# Retro_Programmer-v0_2.net
KiCad netlist of a schematic drawn in EAGLE
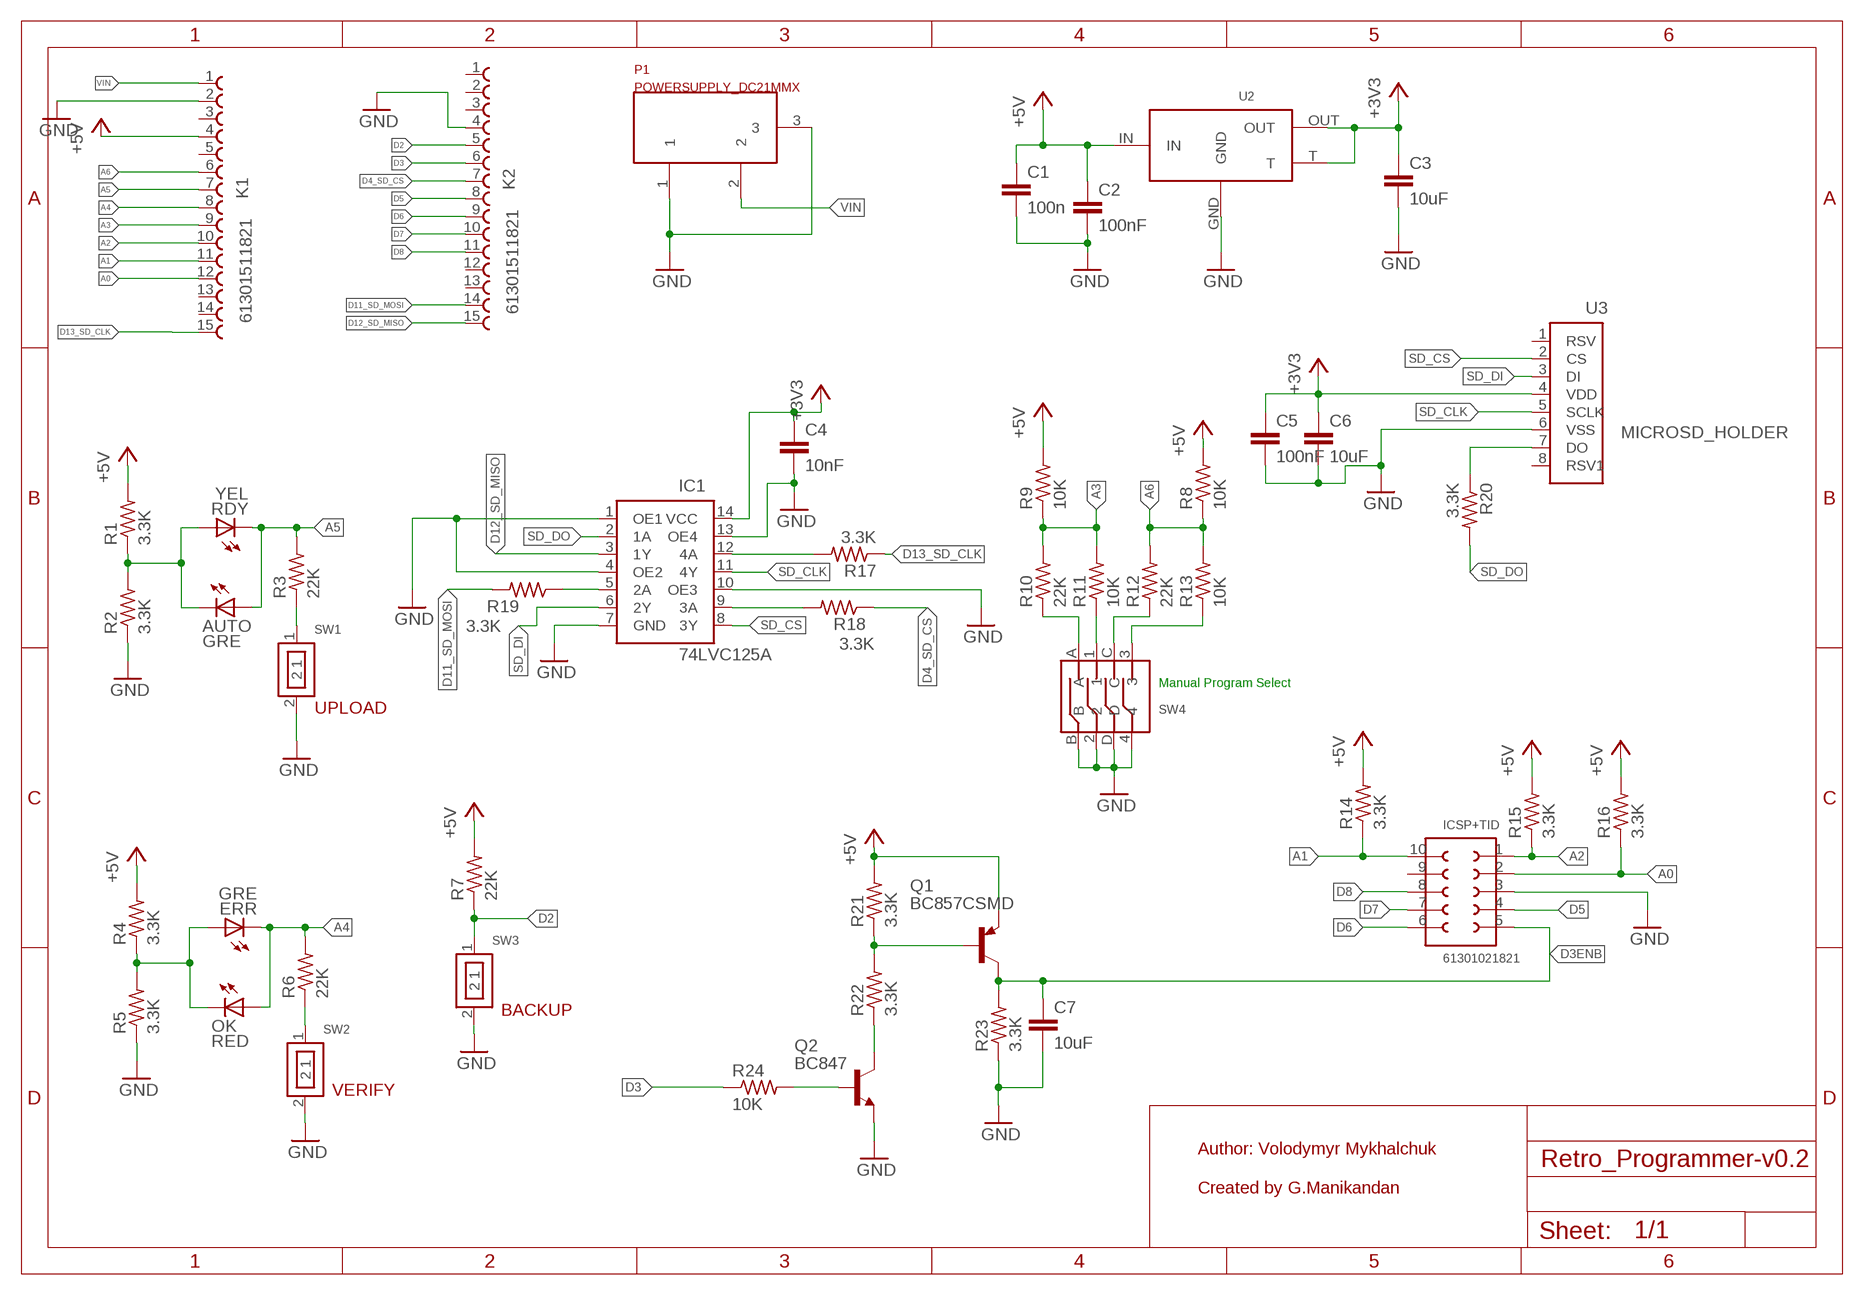
[diagram p0: schematic, sheet 1]

(export (version "E")
  (design (tool "Eeschema 10.0.6"))
  (components
    (comp (ref "AUTO")
      (value "GRE")
      (footprint "eagle-import:CHIPLED_1206")
      (libsource (lib "eagle-import") (part "LEDCHIPLED_1206"))
    )
    (comp (ref "C1")
      (value "100n")
      (footprint "eagle-import:C1206")
      (libsource (lib "eagle-import") (part "C-EUC1206"))
    )
    (comp (ref "C2")
      (value "100nF")
      (footprint "eagle-import:C1206")
      (libsource (lib "eagle-import") (part "C-EUC1206"))
    )
    (comp (ref "C3")
      (value "10uF")
      (footprint "eagle-import:C1206")
      (libsource (lib "eagle-import") (part "C-EUC1206"))
    )
    (comp (ref "C4")
      (value "10nF")
      (footprint "eagle-import:C1206")
      (libsource (lib "eagle-import") (part "C-EUC1206"))
    )
    (comp (ref "C5")
      (value "100nF")
      (footprint "eagle-import:C1206")
      (libsource (lib "eagle-import") (part "C-EUC1206"))
    )
    (comp (ref "C6")
      (value "10uF")
      (footprint "eagle-import:C1206")
      (libsource (lib "eagle-import") (part "C-EUC1206"))
    )
    (comp (ref "C7")
      (value "10uF")
      (footprint "eagle-import:C1206")
      (libsource (lib "eagle-import") (part "C-EUC1206"))
    )
    (comp (ref "ERR")
      (value "GRE")
      (footprint "eagle-import:CHIPLED_1206")
      (libsource (lib "eagle-import") (part "LEDCHIPLED_1206"))
    )
    (comp (ref "IC1")
      (value "74LVC125A")
      (footprint "eagle-import:SOIC14_74L")
      (libsource (lib "eagle-import") (part "74LVC125A"))
    )
    (comp (ref "ICSP+TID")
      (value "61301021821")
      (footprint "eagle-import:61301021821")
      (libsource (lib "eagle-import") (part "61301021821"))
    )
    (comp (ref "K1")
      (value "61301511821")
      (footprint "eagle-import:61301511821")
      (libsource (lib "eagle-import") (part "61301511821"))
    )
    (comp (ref "K2")
      (value "61301511821")
      (footprint "eagle-import:61301511821")
      (libsource (lib "eagle-import") (part "61301511821"))
    )
    (comp (ref "OK")
      (value "RED")
      (footprint "eagle-import:CHIPLED_1206")
      (libsource (lib "eagle-import") (part "LEDCHIPLED_1206"))
    )
    (comp (ref "P1")
      (value "POWERSUPPLY_DC21MMX")
      (footprint "eagle-import:POWERSUPPLY_DC-21MM")
      (libsource (lib "eagle-import") (part "POWERSUPPLY_DC21MMX"))
    )
    (comp (ref "Q1")
      (value "BC857CSMD")
      (footprint "eagle-import:SOT23-BEC")
      (libsource (lib "eagle-import") (part "BC857SMDC"))
    )
    (comp (ref "Q2")
      (value "BC847")
      (footprint "eagle-import:SOT23")
      (libsource (lib "eagle-import") (part "BC847"))
    )
    (comp (ref "R1")
      (value "3.3K")
      (footprint "eagle-import:R1206")
      (libsource (lib "eagle-import") (part "R-US_R1206"))
    )
    (comp (ref "R2")
      (value "3.3K")
      (footprint "eagle-import:R1206")
      (libsource (lib "eagle-import") (part "R-US_R1206"))
    )
    (comp (ref "R3")
      (value "22K")
      (footprint "eagle-import:R1206")
      (libsource (lib "eagle-import") (part "R-US_R1206"))
    )
    (comp (ref "R4")
      (value "3.3K")
      (footprint "eagle-import:R1206")
      (libsource (lib "eagle-import") (part "R-US_R1206"))
    )
    (comp (ref "R5")
      (value "3.3K")
      (footprint "eagle-import:R1206")
      (libsource (lib "eagle-import") (part "R-US_R1206"))
    )
    (comp (ref "R6")
      (value "22K")
      (footprint "eagle-import:R1206")
      (libsource (lib "eagle-import") (part "R-US_R1206"))
    )
    (comp (ref "R7")
      (value "22K")
      (footprint "eagle-import:R1206")
      (libsource (lib "eagle-import") (part "R-US_R1206"))
    )
    (comp (ref "R8")
      (value "10K")
      (footprint "eagle-import:R1206")
      (libsource (lib "eagle-import") (part "R-US_R1206"))
    )
    (comp (ref "R9")
      (value "10K")
      (footprint "eagle-import:R1206")
      (libsource (lib "eagle-import") (part "R-US_R1206"))
    )
    (comp (ref "R10")
      (value "22K")
      (footprint "eagle-import:R1206")
      (libsource (lib "eagle-import") (part "R-US_R1206"))
    )
    (comp (ref "R11")
      (value "10K")
      (footprint "eagle-import:R1206")
      (libsource (lib "eagle-import") (part "R-US_R1206"))
    )
    (comp (ref "R12")
      (value "22K")
      (footprint "eagle-import:R1206")
      (libsource (lib "eagle-import") (part "R-US_R1206"))
    )
    (comp (ref "R13")
      (value "10K")
      (footprint "eagle-import:R1206")
      (libsource (lib "eagle-import") (part "R-US_R1206"))
    )
    (comp (ref "R14")
      (value "3.3K")
      (footprint "eagle-import:R1206")
      (libsource (lib "eagle-import") (part "R-US_R1206"))
    )
    (comp (ref "R15")
      (value "3.3K")
      (footprint "eagle-import:R1206")
      (libsource (lib "eagle-import") (part "R-US_R1206"))
    )
    (comp (ref "R16")
      (value "3.3K")
      (footprint "eagle-import:R1206")
      (libsource (lib "eagle-import") (part "R-US_R1206"))
    )
    (comp (ref "R17")
      (value "3.3K")
      (footprint "eagle-import:R1206")
      (libsource (lib "eagle-import") (part "R-US_R1206"))
    )
    (comp (ref "R18")
      (value "3.3K")
      (footprint "eagle-import:R1206")
      (libsource (lib "eagle-import") (part "R-US_R1206"))
    )
    (comp (ref "R19")
      (value "3.3K")
      (footprint "eagle-import:R1206")
      (libsource (lib "eagle-import") (part "R-US_R1206"))
    )
    (comp (ref "R20")
      (value "3.3K")
      (footprint "eagle-import:R1206")
      (libsource (lib "eagle-import") (part "R-US_R1206"))
    )
    (comp (ref "R21")
      (value "3.3K")
      (footprint "eagle-import:R1206")
      (libsource (lib "eagle-import") (part "R-US_R1206"))
    )
    (comp (ref "R22")
      (value "3.3K")
      (footprint "eagle-import:R1206")
      (libsource (lib "eagle-import") (part "R-US_R1206"))
    )
    (comp (ref "R23")
      (value "3.3K")
      (footprint "eagle-import:R1206")
      (libsource (lib "eagle-import") (part "R-US_R1206"))
    )
    (comp (ref "R24")
      (value "10K")
      (footprint "eagle-import:R1206")
      (libsource (lib "eagle-import") (part "R-US_R1206"))
    )
    (comp (ref "RDY")
      (value "YEL")
      (footprint "eagle-import:CHIPLED_1206")
      (libsource (lib "eagle-import") (part "LEDCHIPLED_1206"))
    )
    (comp (ref "SW1")
      (value "SPUSH")
      (footprint "eagle-import:SLIDE1")
      (libsource (lib "eagle-import") (part "SPUSH"))
    )
    (comp (ref "SW2")
      (value "SPUSH")
      (footprint "eagle-import:SLIDE1")
      (libsource (lib "eagle-import") (part "SPUSH"))
    )
    (comp (ref "SW3")
      (value "SPUSH")
      (footprint "eagle-import:SLIDE1")
      (libsource (lib "eagle-import") (part "SPUSH"))
    )
    (comp (ref "SW4")
      (value "SLIDE_WAY4")
      (footprint "eagle-import:SLIDESWITCH_4")
      (libsource (lib "eagle-import") (part "SLIDE_WAY4"))
    )
    (comp (ref "U2")
      (value "LT1117")
      (footprint "eagle-import:SOT223")
      (libsource (lib "eagle-import") (part "LT1117"))
    )
    (comp (ref "U3")
      (value "MICROSD_HOLDER")
      (footprint "eagle-import:SDCARD_HOLDER")
      (libsource (lib "eagle-import") (part "MICROSD_HOLDER"))
    )
  )
  (nets
    (net (code "1") (name "+3V3") (class "Default")
      (node (ref "C3") (pin "1") (pinfunction "1_1") (pintype "passive"))
      (node (ref "C4") (pin "1") (pinfunction "1_1") (pintype "passive"))
      (node (ref "C5") (pin "1") (pinfunction "1_1") (pintype "passive"))
      (node (ref "C6") (pin "1") (pinfunction "1_1") (pintype "passive"))
      (node (ref "IC1") (pin "14") (pinfunction "VCC_14") (pintype "bidirectional"))
      (node (ref "U2") (pin "OUT") (pinfunction "OUT_OUT") (pintype "bidirectional"))
      (node (ref "U2") (pin "T") (pinfunction "T_T") (pintype "bidirectional"))
      (node (ref "U3") (pin "4") (pinfunction "VDD_4") (pintype "bidirectional"))
    )
    (net (code "2") (name "+5V") (class "Default")
      (node (ref "C1") (pin "1") (pinfunction "1_1") (pintype "passive"))
      (node (ref "C2") (pin "1") (pinfunction "1_1") (pintype "passive"))
      (node (ref "K1") (pin "4") (pinfunction "4_4") (pintype "passive"))
      (node (ref "Q1") (pin "E") (pinfunction "E_E") (pintype "passive"))
      (node (ref "R1") (pin "2") (pinfunction "2_2") (pintype "passive"))
      (node (ref "R14") (pin "2") (pinfunction "2_2") (pintype "passive"))
      (node (ref "R15") (pin "2") (pinfunction "2_2") (pintype "passive"))
      (node (ref "R16") (pin "2") (pinfunction "2_2") (pintype "passive"))
      (node (ref "R21") (pin "2") (pinfunction "2_2") (pintype "passive"))
      (node (ref "R4") (pin "2") (pinfunction "2_2") (pintype "passive"))
      (node (ref "R7") (pin "2") (pinfunction "2_2") (pintype "passive"))
      (node (ref "R8") (pin "2") (pinfunction "2_2") (pintype "passive"))
      (node (ref "R9") (pin "2") (pinfunction "2_2") (pintype "passive"))
      (node (ref "U2") (pin "IN") (pinfunction "IN_IN") (pintype "bidirectional"))
    )
    (net (code "3") (name "A0") (class "Default")
      (node (ref "ICSP+TID") (pin "2") (pinfunction "2_2") (pintype "passive"))
      (node (ref "K1") (pin "12") (pinfunction "12_12") (pintype "passive"))
      (node (ref "R16") (pin "1") (pinfunction "1_1") (pintype "passive"))
    )
    (net (code "4") (name "A1") (class "Default")
      (node (ref "ICSP+TID") (pin "10") (pinfunction "10_10") (pintype "passive"))
      (node (ref "K1") (pin "11") (pinfunction "11_11") (pintype "passive"))
      (node (ref "R14") (pin "1") (pinfunction "1_1") (pintype "passive"))
    )
    (net (code "5") (name "A2") (class "Default")
      (node (ref "ICSP+TID") (pin "1") (pinfunction "1_1") (pintype "passive"))
      (node (ref "K1") (pin "10") (pinfunction "10_10") (pintype "passive"))
      (node (ref "R15") (pin "1") (pinfunction "1_1") (pintype "passive"))
    )
    (net (code "6") (name "A3") (class "Default")
      (node (ref "K1") (pin "9") (pinfunction "9_9") (pintype "passive"))
      (node (ref "R10") (pin "2") (pinfunction "2_2") (pintype "passive"))
      (node (ref "R11") (pin "2") (pinfunction "2_2") (pintype "passive"))
      (node (ref "R9") (pin "1") (pinfunction "1_1") (pintype "passive"))
    )
    (net (code "7") (name "A4") (class "Default")
      (node (ref "ERR") (pin "C") (pinfunction "C_C") (pintype "passive"))
      (node (ref "K1") (pin "8") (pinfunction "8_8") (pintype "passive"))
      (node (ref "OK") (pin "A") (pinfunction "A_A") (pintype "passive"))
      (node (ref "R6") (pin "2") (pinfunction "2_2") (pintype "passive"))
    )
    (net (code "8") (name "A5") (class "Default")
      (node (ref "AUTO") (pin "A") (pinfunction "A_A") (pintype "passive"))
      (node (ref "K1") (pin "7") (pinfunction "7_7") (pintype "passive"))
      (node (ref "R3") (pin "2") (pinfunction "2_2") (pintype "passive"))
      (node (ref "RDY") (pin "C") (pinfunction "C_C") (pintype "passive"))
    )
    (net (code "9") (name "A6") (class "Default")
      (node (ref "K1") (pin "6") (pinfunction "6_6") (pintype "passive"))
      (node (ref "R12") (pin "2") (pinfunction "2_2") (pintype "passive"))
      (node (ref "R13") (pin "2") (pinfunction "2_2") (pintype "passive"))
      (node (ref "R8") (pin "1") (pinfunction "1_1") (pintype "passive"))
    )
    (net (code "10") (name "D2") (class "Default")
      (node (ref "K2") (pin "5") (pinfunction "5_5") (pintype "passive"))
      (node (ref "R7") (pin "1") (pinfunction "1_1") (pintype "passive"))
      (node (ref "SW3") (pin "1") (pinfunction "1_1") (pintype "bidirectional"))
    )
    (net (code "11") (name "D3") (class "Default")
      (node (ref "K2") (pin "6") (pinfunction "6_6") (pintype "passive"))
      (node (ref "R24") (pin "1") (pinfunction "1_1") (pintype "passive"))
    )
    (net (code "12") (name "D3ENB") (class "Default")
      (node (ref "C7") (pin "1") (pinfunction "1_1") (pintype "passive"))
      (node (ref "ICSP+TID") (pin "5") (pinfunction "5_5") (pintype "passive"))
      (node (ref "Q1") (pin "C") (pinfunction "C_C") (pintype "passive"))
      (node (ref "R23") (pin "2") (pinfunction "2_2") (pintype "passive"))
    )
    (net (code "13") (name "D4_SD_CS") (class "Default")
      (node (ref "K2") (pin "7") (pinfunction "7_7") (pintype "passive"))
      (node (ref "R18") (pin "1") (pinfunction "1_1") (pintype "passive"))
    )
    (net (code "14") (name "D5") (class "Default")
      (node (ref "ICSP+TID") (pin "4") (pinfunction "4_4") (pintype "passive"))
      (node (ref "K2") (pin "8") (pinfunction "8_8") (pintype "passive"))
    )
    (net (code "15") (name "D6") (class "Default")
      (node (ref "ICSP+TID") (pin "6") (pinfunction "6_6") (pintype "passive"))
      (node (ref "K2") (pin "9") (pinfunction "9_9") (pintype "passive"))
    )
    (net (code "16") (name "D7") (class "Default")
      (node (ref "ICSP+TID") (pin "7") (pinfunction "7_7") (pintype "passive"))
      (node (ref "K2") (pin "10") (pinfunction "10_10") (pintype "passive"))
    )
    (net (code "17") (name "D8") (class "Default")
      (node (ref "ICSP+TID") (pin "8") (pinfunction "8_8") (pintype "passive"))
      (node (ref "K2") (pin "11") (pinfunction "11_11") (pintype "passive"))
    )
    (net (code "18") (name "D11_SD_MOSI") (class "Default")
      (node (ref "K2") (pin "14") (pinfunction "14_14") (pintype "passive"))
      (node (ref "R19") (pin "2") (pinfunction "2_2") (pintype "passive"))
    )
    (net (code "19") (name "D12_SD_MISO") (class "Default")
      (node (ref "IC1") (pin "3") (pinfunction "1Y_3") (pintype "bidirectional"))
      (node (ref "K2") (pin "15") (pinfunction "15_15") (pintype "passive"))
    )
    (net (code "20") (name "D13_SD_CLK") (class "Default")
      (node (ref "K1") (pin "15") (pinfunction "15_15") (pintype "passive"))
      (node (ref "R17") (pin "1") (pinfunction "1_1") (pintype "passive"))
    )
    (net (code "21") (name "GND") (class "Default")
      (node (ref "C1") (pin "2") (pinfunction "2_2") (pintype "passive"))
      (node (ref "C2") (pin "2") (pinfunction "2_2") (pintype "passive"))
      (node (ref "C3") (pin "2") (pinfunction "2_2") (pintype "passive"))
      (node (ref "C4") (pin "2") (pinfunction "2_2") (pintype "passive"))
      (node (ref "C5") (pin "2") (pinfunction "2_2") (pintype "passive"))
      (node (ref "C6") (pin "2") (pinfunction "2_2") (pintype "passive"))
      (node (ref "C7") (pin "2") (pinfunction "2_2") (pintype "passive"))
      (node (ref "IC1") (pin "1") (pinfunction "OE1_1") (pintype "bidirectional"))
      (node (ref "IC1") (pin "10") (pinfunction "OE3_10") (pintype "bidirectional"))
      (node (ref "IC1") (pin "13") (pinfunction "OE4_13") (pintype "bidirectional"))
      (node (ref "IC1") (pin "4") (pinfunction "OE2_4") (pintype "bidirectional"))
      (node (ref "IC1") (pin "7") (pinfunction "GND_7") (pintype "bidirectional"))
      (node (ref "ICSP+TID") (pin "3") (pinfunction "3_3") (pintype "passive"))
      (node (ref "K1") (pin "2") (pinfunction "2_2") (pintype "passive"))
      (node (ref "K2") (pin "4") (pinfunction "4_4") (pintype "passive"))
      (node (ref "P1") (pin "1") (pinfunction "1_1") (pintype "power_in"))
      (node (ref "P1") (pin "3") (pinfunction "3_3") (pintype "power_in"))
      (node (ref "Q2") (pin "2") (pinfunction "E_2") (pintype "passive"))
      (node (ref "R2") (pin "1") (pinfunction "1_1") (pintype "passive"))
      (node (ref "R23") (pin "1") (pinfunction "1_1") (pintype "passive"))
      (node (ref "R5") (pin "1") (pinfunction "1_1") (pintype "passive"))
      (node (ref "SW1") (pin "2") (pinfunction "2_2") (pintype "bidirectional"))
      (node (ref "SW2") (pin "2") (pinfunction "2_2") (pintype "bidirectional"))
      (node (ref "SW3") (pin "2") (pinfunction "2_2") (pintype "bidirectional"))
      (node (ref "SW4") (pin "2") (pinfunction "2_2") (pintype "bidirectional"))
      (node (ref "SW4") (pin "4") (pinfunction "4_4") (pintype "bidirectional"))
      (node (ref "SW4") (pin "B") (pinfunction "B_B") (pintype "bidirectional"))
      (node (ref "SW4") (pin "D") (pinfunction "D_D") (pintype "bidirectional"))
      (node (ref "U2") (pin "GND") (pinfunction "GND_GND") (pintype "bidirectional"))
      (node (ref "U3") (pin "6") (pinfunction "VSS_6") (pintype "bidirectional"))
    )
    (net (code "22") (name "Net-(AUTO-PadC)") (class "Default")
      (node (ref "AUTO") (pin "C") (pinfunction "C_C") (pintype "passive"))
      (node (ref "R1") (pin "1") (pinfunction "1_1") (pintype "passive"))
      (node (ref "R2") (pin "2") (pinfunction "2_2") (pintype "passive"))
      (node (ref "RDY") (pin "A") (pinfunction "A_A") (pintype "passive"))
    )
    (net (code "23") (name "Net-(ERR-PadA)") (class "Default")
      (node (ref "ERR") (pin "A") (pinfunction "A_A") (pintype "passive"))
      (node (ref "OK") (pin "C") (pinfunction "C_C") (pintype "passive"))
      (node (ref "R4") (pin "1") (pinfunction "1_1") (pintype "passive"))
      (node (ref "R5") (pin "2") (pinfunction "2_2") (pintype "passive"))
    )
    (net (code "24") (name "Net-(IC1-2A)") (class "Default")
      (node (ref "IC1") (pin "5") (pinfunction "2A_5") (pintype "bidirectional"))
      (node (ref "R19") (pin "1") (pinfunction "1_1") (pintype "passive"))
    )
    (net (code "25") (name "Net-(IC1-3A)") (class "Default")
      (node (ref "IC1") (pin "9") (pinfunction "3A_9") (pintype "bidirectional"))
      (node (ref "R18") (pin "2") (pinfunction "2_2") (pintype "passive"))
    )
    (net (code "26") (name "Net-(IC1-4A)") (class "Default")
      (node (ref "IC1") (pin "12") (pinfunction "4A_12") (pintype "bidirectional"))
      (node (ref "R17") (pin "2") (pinfunction "2_2") (pintype "passive"))
    )
    (net (code "27") (name "Net-(Q1-PadB)") (class "Default")
      (node (ref "Q1") (pin "B") (pinfunction "B_B") (pintype "passive"))
      (node (ref "R21") (pin "1") (pinfunction "1_1") (pintype "passive"))
      (node (ref "R22") (pin "2") (pinfunction "2_2") (pintype "passive"))
    )
    (net (code "28") (name "Net-(Q2-B)") (class "Default")
      (node (ref "Q2") (pin "1") (pinfunction "B_1") (pintype "passive"))
      (node (ref "R24") (pin "2") (pinfunction "2_2") (pintype "passive"))
    )
    (net (code "29") (name "Net-(Q2-C)") (class "Default")
      (node (ref "Q2") (pin "3") (pinfunction "C_3") (pintype "passive"))
      (node (ref "R22") (pin "1") (pinfunction "1_1") (pintype "passive"))
    )
    (net (code "30") (name "Net-(R3-Pad1)") (class "Default")
      (node (ref "R3") (pin "1") (pinfunction "1_1") (pintype "passive"))
      (node (ref "SW1") (pin "1") (pinfunction "1_1") (pintype "bidirectional"))
    )
    (net (code "31") (name "Net-(R6-Pad1)") (class "Default")
      (node (ref "R6") (pin "1") (pinfunction "1_1") (pintype "passive"))
      (node (ref "SW2") (pin "1") (pinfunction "1_1") (pintype "bidirectional"))
    )
    (net (code "32") (name "Net-(R10-Pad1)") (class "Default")
      (node (ref "R10") (pin "1") (pinfunction "1_1") (pintype "passive"))
      (node (ref "SW4") (pin "A") (pinfunction "A_A") (pintype "bidirectional"))
    )
    (net (code "33") (name "Net-(R11-Pad1)") (class "Default")
      (node (ref "R11") (pin "1") (pinfunction "1_1") (pintype "passive"))
      (node (ref "SW4") (pin "1") (pinfunction "1_1") (pintype "bidirectional"))
    )
    (net (code "34") (name "Net-(R12-Pad1)") (class "Default")
      (node (ref "R12") (pin "1") (pinfunction "1_1") (pintype "passive"))
      (node (ref "SW4") (pin "C") (pinfunction "C_C") (pintype "bidirectional"))
    )
    (net (code "35") (name "Net-(R13-Pad1)") (class "Default")
      (node (ref "R13") (pin "1") (pinfunction "1_1") (pintype "passive"))
      (node (ref "SW4") (pin "3") (pinfunction "3_3") (pintype "bidirectional"))
    )
    (net (code "36") (name "Net-(U3-DO)") (class "Default")
      (node (ref "R20") (pin "1") (pinfunction "1_1") (pintype "passive"))
      (node (ref "U3") (pin "7") (pinfunction "DO_7") (pintype "bidirectional"))
    )
    (net (code "37") (name "SD_CLK") (class "Default")
      (node (ref "IC1") (pin "11") (pinfunction "4Y_11") (pintype "bidirectional"))
      (node (ref "U3") (pin "5") (pinfunction "SCLK_5") (pintype "bidirectional"))
    )
    (net (code "38") (name "SD_CS") (class "Default")
      (node (ref "IC1") (pin "8") (pinfunction "3Y_8") (pintype "bidirectional"))
      (node (ref "U3") (pin "2") (pinfunction "CS_2") (pintype "bidirectional"))
    )
    (net (code "39") (name "SD_DI") (class "Default")
      (node (ref "IC1") (pin "6") (pinfunction "2Y_6") (pintype "bidirectional"))
      (node (ref "U3") (pin "3") (pinfunction "DI_3") (pintype "bidirectional"))
    )
    (net (code "40") (name "SD_DO") (class "Default")
      (node (ref "IC1") (pin "2") (pinfunction "1A_2") (pintype "bidirectional"))
      (node (ref "R20") (pin "2") (pinfunction "2_2") (pintype "passive"))
    )
    (net (code "41") (name "VIN") (class "Default")
      (node (ref "K1") (pin "1") (pinfunction "1_1") (pintype "passive"))
      (node (ref "P1") (pin "2") (pinfunction "2_2") (pintype "power_in"))
    )
    (net (code "42") (name "unconnected-(ICSP+TID-Pad9)") (class "Default")
      (node (ref "ICSP+TID") (pin "9") (pinfunction "9_9") (pintype "passive"))
    )
    (net (code "43") (name "unconnected-(K1-Pad3)") (class "Default")
      (node (ref "K1") (pin "3") (pinfunction "3_3") (pintype "passive"))
    )
    (net (code "44") (name "unconnected-(K1-Pad5)") (class "Default")
      (node (ref "K1") (pin "5") (pinfunction "5_5") (pintype "passive"))
    )
    (net (code "45") (name "unconnected-(K1-Pad13)") (class "Default")
      (node (ref "K1") (pin "13") (pinfunction "13_13") (pintype "passive"))
    )
    (net (code "46") (name "unconnected-(K1-Pad14)") (class "Default")
      (node (ref "K1") (pin "14") (pinfunction "14_14") (pintype "passive"))
    )
    (net (code "47") (name "unconnected-(K2-Pad1)") (class "Default")
      (node (ref "K2") (pin "1") (pinfunction "1_1") (pintype "passive"))
    )
    (net (code "48") (name "unconnected-(K2-Pad2)") (class "Default")
      (node (ref "K2") (pin "2") (pinfunction "2_2") (pintype "passive"))
    )
    (net (code "49") (name "unconnected-(K2-Pad3)") (class "Default")
      (node (ref "K2") (pin "3") (pinfunction "3_3") (pintype "passive"))
    )
    (net (code "50") (name "unconnected-(K2-Pad12)") (class "Default")
      (node (ref "K2") (pin "12") (pinfunction "12_12") (pintype "passive"))
    )
    (net (code "51") (name "unconnected-(K2-Pad13)") (class "Default")
      (node (ref "K2") (pin "13") (pinfunction "13_13") (pintype "passive"))
    )
    (net (code "52") (name "unconnected-(U3-RSV-Pad1)") (class "Default")
      (node (ref "U3") (pin "1") (pinfunction "RSV_1") (pintype "bidirectional"))
    )
    (net (code "53") (name "unconnected-(U3-RSV1-Pad8)") (class "Default")
      (node (ref "U3") (pin "8") (pinfunction "RSV1_8") (pintype "bidirectional"))
    )
  )
)
